# DM1097_RJ45.net
KiCad netlist of a schematic drawn in Altium Designer
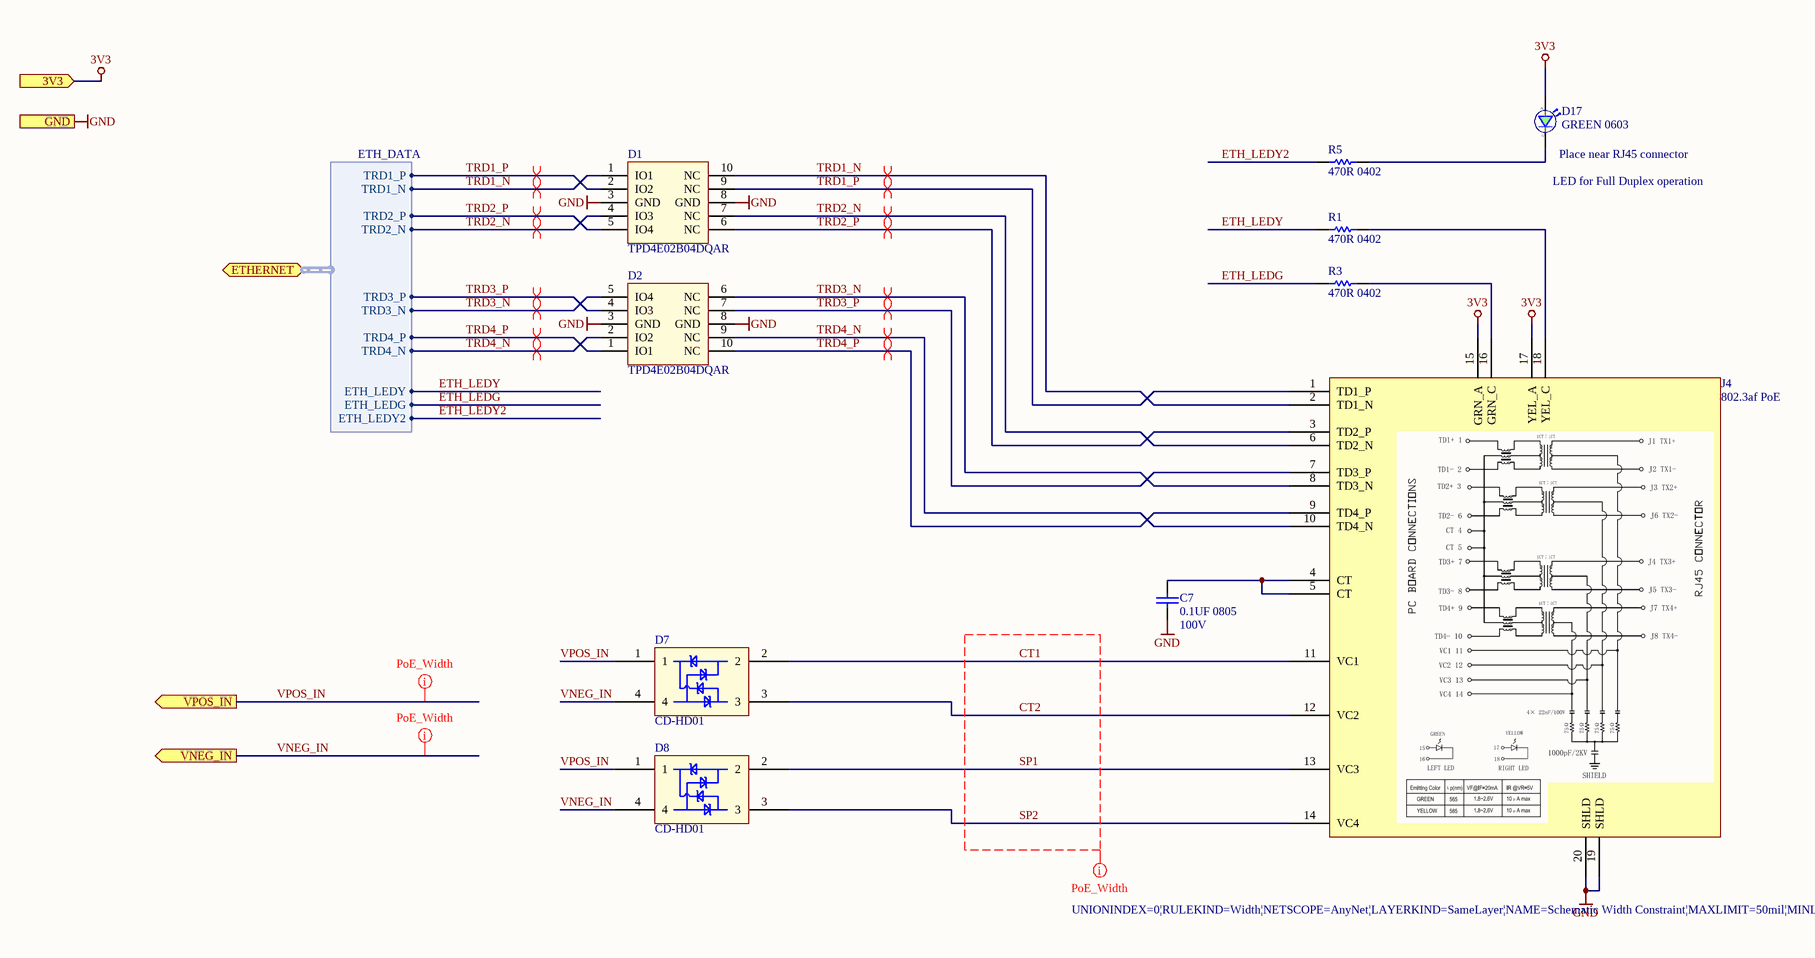
[diagram p0: DM1097_RJ45.SchDoc]

(export (version "E")
  (design (tool "Eeschema 10.0.6"))
  (components
    (comp (ref "C7")
      (value "0.1UF 0805")
      (footprint "CAPC0805(2012)145_N")
      (description "CAP CER 0.1UF 100V X7R 0805")
      (fields (field (name "TOLERANCE") "10%") (field (name "VOLTAGE RATING") "100V"))
      (libsource (lib "DM1097_SchLib") (part "CL21B104KCFNNNE"))
    )
    (comp (ref "D1")
      (value "TPD4E02B04DQAR")
      (footprint "LuxonisMaster:TPD4E02B04DQAR")
      (libsource (lib "") (part "TPD4E02B04DQAR_1"))
    )
    (comp (ref "D2")
      (value "TPD4E02B04DQAR")
      (footprint "LuxonisMaster:TPD4E02B04DQAR")
      (libsource (lib "LuxonisMaster") (part "TPD4E02B04DQAR"))
    )
    (comp (ref "D7")
      (value "CD-HD01")
      (footprint "CD-H01")
      (description "CD-HD0x Series Schottky Bridge Rectifier Diode 100V 4-Pin Surface Mount T/R")
      (libsource (lib "DM1097_R1M1E1") (part "CD-HD01"))
    )
    (comp (ref "D8")
      (value "CD-HD01")
      (footprint "CD-H01")
      (description "CD-HD0x Series Schottky Bridge Rectifier Diode 100V 4-Pin Surface Mount T/R")
      (libsource (lib "DM1097_R1M1E1") (part "CD-HD01"))
    )
    (comp (ref "D17")
      (value "GREEN 0603")
      (footprint "LuxonisMaster:SML_D1xx8W")
      (description "LED GREEN DIFFUSED 0603 SMD Green 572nm LED Indication - Discrete 2.2V 0603 (1608 Metric)")
      (fields (field (name "MANUFACTURER") "Rohm") (field (name "MANUFACTURER PART NUMBER") "SML-D12M8WT86"))
      (libsource (lib "LuxonisMaster") (part "SML-D12M8WT86"))
    )
    (comp (ref "J4")
      (value "802.3af PoE")
      (footprint "TRJG0926HENL")
      (description "CONN MAGJACK 1PORT 1000 BASET")
      (libsource (lib "DM1097_SchLib") (part "TRJG0926HENL"))
    )
    (comp (ref "R1")
      (value "470R 0402")
      (footprint "RES_Altium_Vault_Generic:RESC0402(1005)_N")
      (description "RES SMD 470 OHM 1% 1/16W 0402")
      (fields (field (name "TOLERANCE") "1%"))
      (libsource (lib "LuxonisMaster") (part "CRCW0402470RFKED"))
    )
    (comp (ref "R3")
      (value "470R 0402")
      (footprint "RES_Altium_Vault_Generic:RESC0402(1005)_N")
      (description "RES SMD 470 OHM 1% 1/16W 0402")
      (fields (field (name "TOLERANCE") "1%"))
      (libsource (lib "LuxonisMaster") (part "CRCW0402470RFKED"))
    )
    (comp (ref "R5")
      (value "470R 0402")
      (footprint "RES_Altium_Vault_Generic:RESC0402(1005)_N")
      (description "RES SMD 470 OHM 1% 1/16W 0402")
      (fields (field (name "TOLERANCE") "1%"))
      (libsource (lib "LuxonisMaster") (part "CRCW0402470RFKED"))
    )
  )
  (nets
    (net (code "2") (name "/CT1") (class "Default")
      (node (ref "D7") (pin "2") (pinfunction "2_2") (pintype "passive"))
      (node (ref "J4") (pin "11") (pinfunction "VC1_11") (pintype "passive"))
    )
    (net (code "3") (name "/CT2") (class "Default")
      (node (ref "D7") (pin "3") (pinfunction "3_3") (pintype "passive"))
      (node (ref "J4") (pin "12") (pinfunction "VC2_12") (pintype "passive"))
    )
    (net (code "4") (name "/ETH_LEDG") (class "Default")
      (node (ref "R3") (pin "1") (pinfunction "1_1") (pintype "passive"))
    )
    (net (code "5") (name "/ETH_LEDY") (class "Default")
      (node (ref "R1") (pin "1") (pinfunction "1_1") (pintype "passive"))
    )
    (net (code "6") (name "/ETH_LEDY2") (class "Default")
      (node (ref "R5") (pin "1") (pinfunction "1_1") (pintype "passive"))
    )
    (net (code "7") (name "/SP1") (class "Default")
      (node (ref "D8") (pin "2") (pinfunction "2_2") (pintype "passive"))
      (node (ref "J4") (pin "13") (pinfunction "VC3_13") (pintype "passive"))
    )
    (net (code "8") (name "/SP2") (class "Default")
      (node (ref "D8") (pin "3") (pinfunction "3_3") (pintype "passive"))
      (node (ref "J4") (pin "14") (pinfunction "VC4_14") (pintype "passive"))
    )
    (net (code "9") (name "/TRD1_N") (class "Default")
      (node (ref "D1") (pin "1") (pinfunction "IO1_1") (pintype "passive"))
      (node (ref "D1") (pin "10") (pinfunction "NC_10") (pintype "passive"))
      (node (ref "J4") (pin "2") (pinfunction "TD1_N_2") (pintype "passive"))
    )
    (net (code "10") (name "/TRD1_P") (class "Default")
      (node (ref "D1") (pin "2") (pinfunction "IO2_2") (pintype "passive"))
      (node (ref "D1") (pin "9") (pinfunction "NC_9") (pintype "passive"))
      (node (ref "J4") (pin "1") (pinfunction "TD1_P_1") (pintype "passive"))
    )
    (net (code "11") (name "/TRD2_N") (class "Default")
      (node (ref "D1") (pin "4") (pinfunction "IO3_4") (pintype "passive"))
      (node (ref "D1") (pin "7") (pinfunction "NC_7") (pintype "passive"))
      (node (ref "J4") (pin "6") (pinfunction "TD2_N_6") (pintype "passive"))
    )
    (net (code "12") (name "/TRD2_P") (class "Default")
      (node (ref "D1") (pin "5") (pinfunction "IO4_5") (pintype "passive"))
      (node (ref "D1") (pin "6") (pinfunction "NC_6") (pintype "passive"))
      (node (ref "J4") (pin "3") (pinfunction "TD2_P_3") (pintype "passive"))
    )
    (net (code "13") (name "/TRD3_N") (class "Default")
      (node (ref "D2") (pin "5") (pinfunction "IO4_5") (pintype "passive"))
      (node (ref "D2") (pin "6") (pinfunction "NC_6") (pintype "passive"))
      (node (ref "J4") (pin "8") (pinfunction "TD3_N_8") (pintype "passive"))
    )
    (net (code "14") (name "/TRD3_P") (class "Default")
      (node (ref "D2") (pin "4") (pinfunction "IO3_4") (pintype "passive"))
      (node (ref "D2") (pin "7") (pinfunction "NC_7") (pintype "passive"))
      (node (ref "J4") (pin "7") (pinfunction "TD3_P_7") (pintype "passive"))
    )
    (net (code "15") (name "/TRD4_N") (class "Default")
      (node (ref "D2") (pin "2") (pinfunction "IO2_2") (pintype "passive"))
      (node (ref "D2") (pin "9") (pinfunction "NC_9") (pintype "passive"))
      (node (ref "J4") (pin "10") (pinfunction "TD4_N_10") (pintype "passive"))
    )
    (net (code "16") (name "/TRD4_P") (class "Default")
      (node (ref "D2") (pin "1") (pinfunction "IO1_1") (pintype "passive"))
      (node (ref "D2") (pin "10") (pinfunction "NC_10") (pintype "passive"))
      (node (ref "J4") (pin "9") (pinfunction "TD4_P_9") (pintype "passive"))
    )
    (net (code "17") (name "/VNEG_IN") (class "Default")
      (node (ref "D7") (pin "4") (pinfunction "4_4") (pintype "passive"))
      (node (ref "D8") (pin "4") (pinfunction "4_4") (pintype "passive"))
    )
    (net (code "18") (name "/VPOS_IN") (class "Default")
      (node (ref "D7") (pin "1") (pinfunction "1_1") (pintype "passive"))
      (node (ref "D8") (pin "1") (pinfunction "1_1") (pintype "passive"))
    )
    (net (code "20") (name "3V3") (class "Default")
      (node (ref "D17") (pin "2") (pinfunction "A_2") (pintype "passive"))
      (node (ref "J4") (pin "15") (pinfunction "GRN_A_15") (pintype "passive"))
      (node (ref "J4") (pin "17") (pinfunction "YEL_A_17") (pintype "passive"))
    )
    (net (code "21") (name "GND") (class "Default")
      (node (ref "C7") (pin "1") (pinfunction "1_1") (pintype "passive"))
      (node (ref "D1") (pin "3") (pinfunction "GND_3") (pintype "passive"))
      (node (ref "D1") (pin "8") (pinfunction "GND_8") (pintype "passive"))
      (node (ref "D2") (pin "3") (pinfunction "GND_3") (pintype "passive"))
      (node (ref "D2") (pin "8") (pinfunction "GND_8") (pintype "passive"))
      (node (ref "J4") (pin "19") (pinfunction "SHLD_19") (pintype "passive"))
      (node (ref "J4") (pin "20") (pinfunction "SHLD_20") (pintype "passive"))
    )
    (net (code "22") (name "Net-(C7-Pad2)") (class "Default")
      (node (ref "C7") (pin "2") (pinfunction "2_2") (pintype "passive"))
      (node (ref "J4") (pin "4") (pinfunction "CT_4") (pintype "passive"))
      (node (ref "J4") (pin "5") (pinfunction "CT_5") (pintype "passive"))
    )
    (net (code "23") (name "Net-(D17-C)") (class "Default")
      (node (ref "D17") (pin "1") (pinfunction "C_1") (pintype "passive"))
      (node (ref "R5") (pin "2") (pinfunction "2_2") (pintype "passive"))
    )
    (net (code "24") (name "Net-(J4-GRN_C)") (class "Default")
      (node (ref "J4") (pin "16") (pinfunction "GRN_C_16") (pintype "passive"))
      (node (ref "R3") (pin "2") (pinfunction "2_2") (pintype "passive"))
    )
    (net (code "25") (name "Net-(J4-YEL_C)") (class "Default")
      (node (ref "J4") (pin "18") (pinfunction "YEL_C_18") (pintype "passive"))
      (node (ref "R1") (pin "2") (pinfunction "2_2") (pintype "passive"))
    )
  )
)
